# Input.net
KiCad netlist of a schematic drawn in Altium Designer
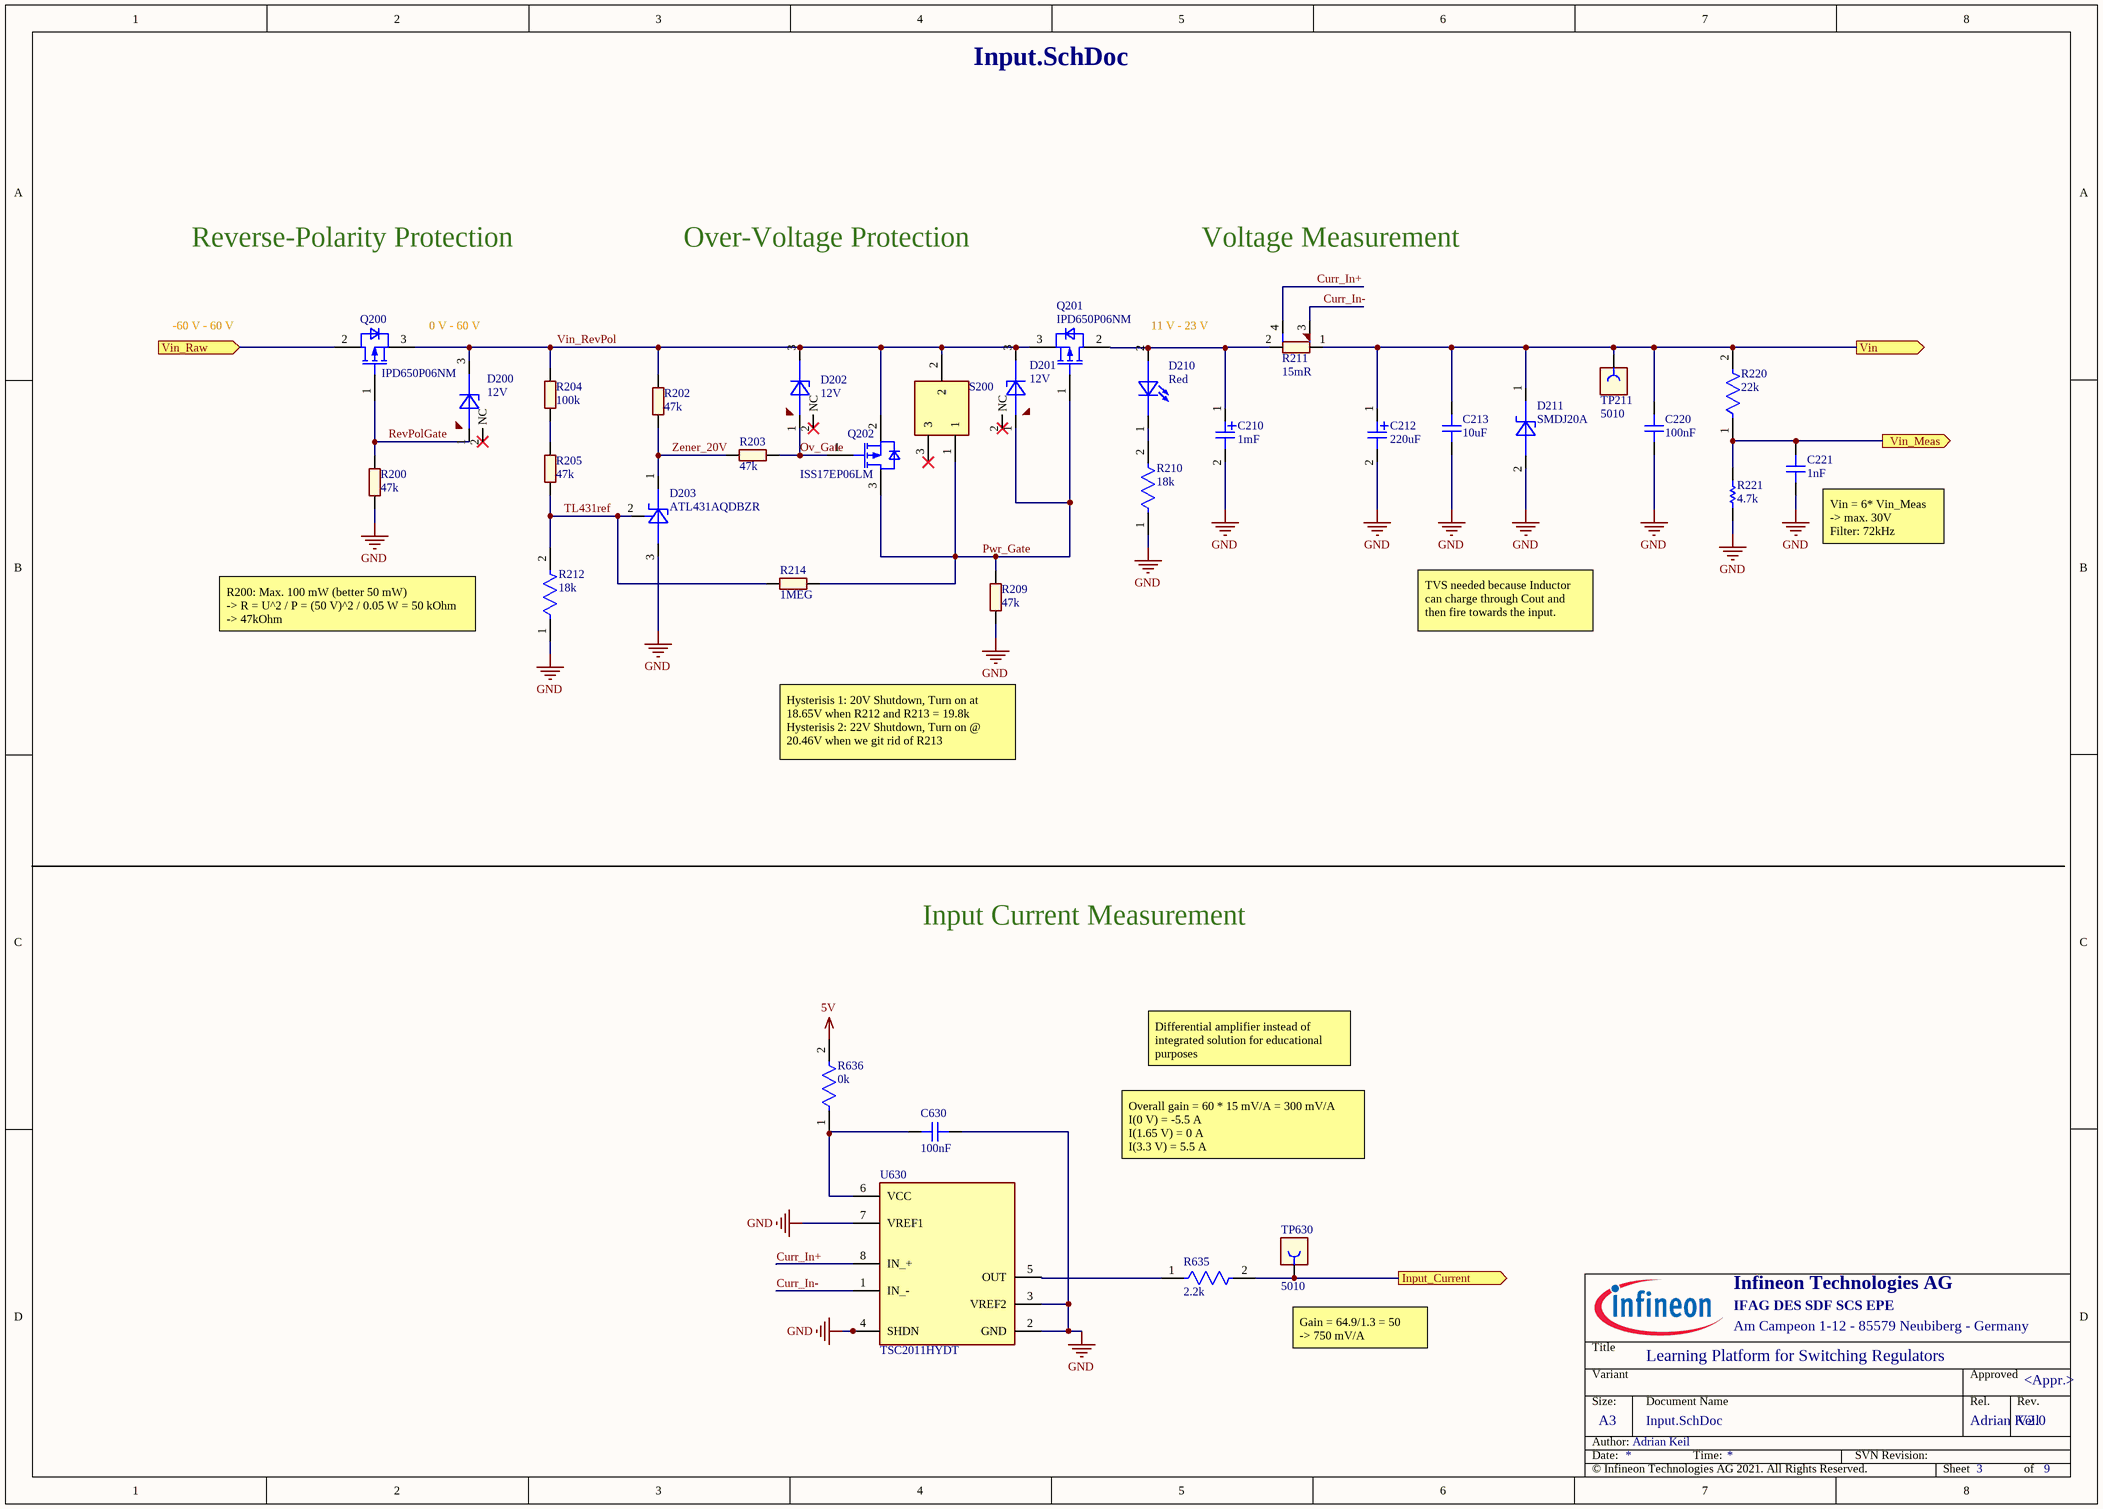
[diagram p0: Input.SchDoc]

(export (version "E")
  (design (tool "Eeschema 10.0.6"))
  (components
    (comp (ref "C210")
      (value "1mF")
      (footprint "CAPPRD500W60D1300H2700B")
      (fields (field (name "MANUFACTURER") "Kemet") (field (name "MPN") "ESY108M035AL4AA"))
      (libsource (lib "PCBLibraryData") (part "CAP-SGL-POL-02P_00000002"))
    )
    (comp (ref "C212")
      (value "220uF")
      (footprint "CAPAE1030X1050N-3")
      (fields
        (field (name "MANUFACTURER") "Nippon Chemi-Con")
        (field (name "LCSC PART #") "C6845235")
        (field (name "MPN") "EMZL500ARA221MJA0G")
      )
      (libsource (lib "PCBLibraryData") (part "CAP-SGL-POL-02P_00000002"))
    )
    (comp (ref "C213")
      (value "10uF")
      (footprint "CAPC3216X190N-1")
      (description "CAP / CERA / 10uF / 50V / 20% / X5R (EIA) / -55°C to 85°C / 1206 (3216) / SMD / -")
      (fields (field (name "MANUFACTURER") "Taiyo Yuden") (field (name "MPN") "UMK316BBJ106ML-T"))
      (libsource (lib "PCBLibraryData") (part "CAP-SGL-STD-02P_00000001"))
    )
    (comp (ref "C220")
      (value "100nF")
      (footprint "CAPC3216X125N-0")
      (description "CAP / CERA / 100nF / 50V / 10% / X7R (EIA) / -55°C to 125°C / 1206(3216) / SMD / -")
      (fields (field (name "LEGACY PARTNUMBER") "CAP01005660") (field (name "MANUFACTURER") "MuRata"))
      (libsource (lib "PCBLibraryData") (part "CAP-SGL-STD-02P_00000001"))
    )
    (comp (ref "C221")
      (value "1nF")
      (footprint "CAPC3216X95N")
      (description "CAP / CERA / 1nF / 50V / 10% / X7R (EIA) / -55°C to 125°C / 1206(3216) / SMD / -")
      (fields (field (name "LEGACY PARTNUMBER") "CAP01005183") (field (name "MANUFACTURER") "MuRata"))
      (libsource (lib "PCBLibraryData") (part "CAP-SGL-STD-02P_00000001"))
    )
    (comp (ref "C630")
      (value "100nF")
      (footprint "CAPC3216X125N-0")
      (description "CAP / CERA / 100nF / 50V / 10% / X7R (EIA) / -55°C to 125°C / 1206(3216) / SMD / -")
      (fields (field (name "LEGACY PARTNUMBER") "CAP01005660") (field (name "MANUFACTURER") "MuRata"))
      (libsource (lib "PCBLibraryData") (part "CAP-SGL-STD-02P_00000001"))
    )
    (comp (ref "D200")
      (value "12V")
      (footprint "SOT95P230X110-3N")
      (description "Voltage regulator diodes")
      (fields (field (name "MANUFACTURER") "Nexperia") (field (name "LCSC PART #") "C12773"))
      (libsource (lib "PCBLibraryData") (part "d_zener_a1c3_3p"))
    )
    (comp (ref "D201")
      (value "12V")
      (footprint "SOT95P230X110-3N")
      (description "Voltage regulator diodes")
      (fields (field (name "MANUFACTURER") "Nexperia"))
      (libsource (lib "PCBLibraryData") (part "d_zener_a1c3_3p"))
    )
    (comp (ref "D202")
      (value "12V")
      (footprint "SOT95P230X110-3N")
      (description "Voltage regulator diodes")
      (fields (field (name "MANUFACTURER") "Nexperia"))
      (libsource (lib "PCBLibraryData") (part "d_zener_a1c3_3p"))
    )
    (comp (ref "D203")
      (value "ATL431AQDBZR")
      (footprint "SOT95P237X112-3N-1")
      (description "ATL431 Adjustable Precision Shunt Regulator")
      (fields (field (name "MANUFACTURER") "Texas Instruments") (field (name "LCSC PART #") "C92572"))
      (libsource (lib "PCBLibraryData") (part "d_tvs_c1a3_3p"))
    )
    (comp (ref "D210")
      (value "Red")
      (footprint "LEDSC160X80X80-2N-1")
      (description "WL-SMCW SMT Mono-color Chip LED Waterclear, Red,630nm")
      (fields (field (name "MANUFACTURER") "Wurth Elektronik") (field (name "LCSC PART #") "C3030991"))
      (libsource (lib "PCBLibraryData") (part "d_led_a"))
    )
    (comp (ref "D211")
      (value "SMDJ20A")
      (footprint "DIOM7959X262N")
      (description "TVS Diode, Low Profile Package, Built in Strain Relief, Glass Passivated Chip Junction")
      (fields (field (name "MANUFACTURER") "Littelfuse") (field (name "LCSC PART #") "C2990194"))
      (libsource (lib "PCBLibraryData") (part "d_tvs_a"))
    )
    (comp (ref "Q200")
      (value "IPD650P06NM")
      (footprint "TO228P998X250-3N-V2")
      (description "OptiMOS Power Transistor, -60 V")
      (fields (field (name "MANUFACTURER") "Infineon Technologies") (field (name "MPN") "IPD650P06NMATMA1"))
      (libsource (lib "PCBLibraryData") (part "igfet_p_ch_enh_dio_1g2d3s_3p"))
    )
    (comp (ref "Q201")
      (value "IPD650P06NM")
      (footprint "TO228P998X250-3N-V2")
      (description "OptiMOS Power Transistor, -60 V")
      (fields (field (name "MANUFACTURER") "Infineon Technologies"))
      (libsource (lib "PCBLibraryData") (part "igfet_p_ch_enh_dio_1g2d3s_3p"))
    )
    (comp (ref "Q202")
      (value "ISS17EP06LM")
      (footprint "SOT95P240X110-3N-1-V")
      (description "OptiMOSTM Small Signal Transistor, -60 V")
      (fields (field (name "MANUFACTURER") "Infineon Technologies") (field (name "MPN") "ISS17EP06LMXTSA1"))
      (libsource (lib "PCBLibraryData") (part "igfet_p_ch_enh_dio_1g2s3d_3p"))
    )
    (comp (ref "R200")
      (value "47k")
      (footprint "RESC3216X60N")
      (description "RES / STD / 47k / 250mW / 1% / 100ppm/K / -55°C to 155°C / 1206(3216) / SMD / -")
      (fields (field (name "LEGACY PARTNUMBER") "RES01802933") (field (name "MANUFACTURER") "Vishay"))
      (libsource (lib "") (part "RES-SGL-STD-02P_00000006_1"))
    )
    (comp (ref "R202")
      (value "47k")
      (footprint "RESC3216X60N")
      (description "RES / STD / 47k / 250mW / 1% / 100ppm/K / -55°C to 155°C / 1206(3216) / SMD / -")
      (fields (field (name "LEGACY PARTNUMBER") "RES01802933") (field (name "MANUFACTURER") "Vishay"))
      (libsource (lib "") (part "RES-SGL-STD-02P_00000006_1"))
    )
    (comp (ref "R203")
      (value "47k")
      (footprint "RESC3216X60N")
      (description "RES / STD / 47k / 250mW / 1% / 100ppm/K / -55°C to 155°C / 1206(3216) / SMD / -")
      (fields (field (name "LEGACY PARTNUMBER") "RES01802933") (field (name "MANUFACTURER") "Vishay"))
      (libsource (lib "") (part "RES-SGL-STD-02P_00000006_2"))
    )
    (comp (ref "R204")
      (value "100k")
      (footprint "RESC3216X60N")
      (description "RES / STD / 100k / 250mW / 1% / 100ppm/K / -55°C to 155°C / 1206(3216) / SMD / -")
      (fields (field (name "LEGACY PARTNUMBER") "RES01802971") (field (name "MANUFACTURER") "Vishay"))
      (libsource (lib "PCBLibraryData") (part "RES-SGL-STD-02P_00000006"))
    )
    (comp (ref "R205")
      (value "47k")
      (footprint "RESC3216X60N")
      (description "RES / STD / 47k / 250mW / 1% / 100ppm/K / -55°C to 155°C / 1206(3216) / SMD / -")
      (fields (field (name "LEGACY PARTNUMBER") "RES01802933") (field (name "MANUFACTURER") "Vishay"))
      (libsource (lib "") (part "RES-SGL-STD-02P_00000006_1"))
    )
    (comp (ref "R209")
      (value "47k")
      (footprint "RESC3216X60N")
      (description "RES / STD / 47k / 250mW / 1% / 100ppm/K / -55°C to 155°C / 1206(3216) / SMD / -")
      (fields (field (name "LEGACY PARTNUMBER") "RES01802933") (field (name "MANUFACTURER") "Vishay"))
      (libsource (lib "") (part "RES-SGL-STD-02P_00000006_1"))
    )
    (comp (ref "R210")
      (value "18k")
      (footprint "FP-CRCW1206-e3-IPC_C")
      (description "RES Thick Film, 18kΩ, 1%, 0.25W, 100ppm/°C, 1206")
      (fields (field (name "TOLERANCE") "1%") (field (name "MPN") "CRCW120618K0FKEA"))
      (libsource (lib "Altium Content Vault") (part "1029c3af85768c4190bb7ad29bc67b5"))
    )
    (comp (ref "R211")
      (value "15mR")
      (footprint "RES-SMD-L4T12")
      (description "RES / STD / 15mR / 500mW / 1% / 75ppm/K / -55°C to 155°C / 1206 (3216) / SMD / -")
      (fields (field (name "MANUFACTURER") "Ohmite") (field (name "MPN") "L4T12FR015FER"))
      (libsource (lib "PCBLibraryData") (part "RES-SHT-STD-04P_00097BE5"))
    )
    (comp (ref "R212")
      (value "18k")
      (footprint "FP-CRCW1206-e3-IPC_C")
      (description "RES Thick Film, 18kΩ, 1%, 0.25W, 100ppm/°C, 1206")
      (fields (field (name "TOLERANCE") "1%"))
      (libsource (lib "Altium Content Vault") (part "1029c3af85768c4190bb7ad29bc67b5"))
    )
    (comp (ref "R214")
      (value "1MEG")
      (footprint "RESC3216X60N")
      (description "RES / STD / 1MEG / 250mW / 1% / 100ppm/K / -55°C to 155°C / 1206(3216) / SMD / -")
      (fields (field (name "LEGACY PARTNUMBER") "RES01803085") (field (name "MANUFACTURER") "Vishay"))
      (libsource (lib "") (part "RES-SGL-STD-02P_00000006_3"))
    )
    (comp (ref "R220")
      (value "22k")
      (footprint "FP-CRCW1206-e3-IPC_A")
      (description "RES Thick Film, 22kΩ, 1%, 0.25W, 100ppm/°C, 1206")
      (fields (field (name "TOLERANCE") "1%") (field (name "LCSC PART #") "C844656"))
      (libsource (lib "Altium Content Vault") (part "1029c3af85768c4190bb7ad29bc67b5"))
    )
    (comp (ref "R221")
      (value "4.7k")
      (footprint "RESC3216X60X45ML15T20")
      (description "Chip Resistor, 4.7 KOhm, +/- 1%, 0.25 W, -55 to 155 degC, 1206 (3216 Metric), RoHS, Tape and Reel")
      (fields (field (name "MANUFACTURER") "Vishay Semiconductor") (field (name "TOLERANCE") "1%"))
      (libsource (lib "Altium Content Vault") (part "RES-2"))
    )
    (comp (ref "R635")
      (value "2.2k")
      (footprint "FP-CRCW1206-e3-IPC_C")
      (description "RES Thick Film, 2.2kΩ, 1%, 0.25W, 100ppm/°C, 1206")
      (fields (field (name "TOLERANCE") "1%"))
      (libsource (lib "Altium Content Vault") (part "1029c3af85768c4190bb7ad29bc67b5"))
    )
    (comp (ref "R636")
      (value "0k")
      (footprint "FP-CRCW1206-e3-IPC_C")
      (description "RES Thick Film, 0Ω, 0.25W, 1206")
      (fields (field (name "TOLERANCE") "1%"))
      (libsource (lib "Altium Content Vault") (part "1029c3af85768c4190bb7ad29bc67b5"))
    )
    (comp (ref "S200")
      (value "500SSP1S2M2QEA")
      (footprint "500SSP1S2M2QEA")
      (description "Connector")
      (fields (field (name "MOUSER PART NUMBER") "612-500SSP1S2M2QEA"))
      (libsource (lib "mySchlib") (part "500SSP1S2M2QEA"))
    )
    (comp (ref "TP211")
      (value "5010")
      (footprint "CON-THT-TP-5010")
      (description "PC Test Point-Multipurpose THT, Red")
      (fields
        (field (name "LEGACY PARTNUMBER") "CON01500529")
        (field (name "MANUFACTURER") "Keystone Electronics Corp.")
      )
      (libsource (lib "") (part "connector_1_f_1"))
    )
    (comp (ref "TP630")
      (value "5010")
      (footprint "CON-THT-TP-5010")
      (description "PC Test Point-Multipurpose THT, Red")
      (fields
        (field (name "LEGACY PARTNUMBER") "CON01500529")
        (field (name "MANUFACTURER") "Keystone Electronics Corp.")
      )
      (libsource (lib "PCBLibraryData") (part "connector_1_f"))
    )
    (comp (ref "U630")
      (value "TSC2011HYDT")
      (footprint "myPcbLib:SOIC127P600X175-8N")
      (description "Integrated Circuit")
      (fields (field (name "MOUSER PART NUMBER") "511-TSC2011HYDT"))
      (libsource (lib "mySchlib") (part "TSC2011HYDT"))
    )
  )
  (nets
    (net (code "1") (name "/Curr_In+") (class "Default")
      (node (ref "R211") (pin "4") (pinfunction "I2_4") (pintype "passive"))
      (node (ref "U630") (pin "8") (pinfunction "IN_+_8") (pintype "passive"))
    )
    (net (code "2") (name "/Curr_In-") (class "Default")
      (node (ref "R211") (pin "3") (pinfunction "I1_3") (pintype "passive"))
      (node (ref "U630") (pin "1") (pinfunction "IN_-_1") (pintype "passive"))
    )
    (net (code "3") (name "/Input_Current") (class "Default")
      (node (ref "R635") (pin "2") (pinfunction "2_2") (pintype "passive"))
      (node (ref "TP630") (pin "1") (pinfunction "1_1") (pintype "passive"))
    )
    (net (code "4") (name "/Ov_Gate") (class "Default")
      (node (ref "D202") (pin "1") (pinfunction "ANODE_1") (pintype "passive"))
      (node (ref "Q202") (pin "1") (pinfunction "GATE_1") (pintype "passive"))
      (node (ref "R203") (pin "1") (pinfunction "1_1") (pintype "passive"))
    )
    (net (code "5") (name "/Pwr_Gate") (class "Default")
      (node (ref "D201") (pin "1") (pinfunction "ANODE_1") (pintype "passive"))
      (node (ref "Q201") (pin "1") (pinfunction "GATE_1") (pintype "passive"))
      (node (ref "Q202") (pin "3") (pinfunction "DRAIN_3") (pintype "passive"))
      (node (ref "R209") (pin "2") (pinfunction "2_2") (pintype "passive"))
      (node (ref "R214") (pin "2") (pinfunction "2_2") (pintype "passive"))
      (node (ref "S200") (pin "1") (pinfunction "1_1") (pintype "passive"))
    )
    (net (code "6") (name "/RevPolGate") (class "Default")
      (node (ref "D200") (pin "1") (pinfunction "ANODE_1") (pintype "passive"))
      (node (ref "Q200") (pin "1") (pinfunction "GATE_1") (pintype "passive"))
      (node (ref "R200") (pin "2") (pinfunction "2_2") (pintype "passive"))
    )
    (net (code "7") (name "/TL431ref") (class "Default")
      (node (ref "D203") (pin "2") (pinfunction "REF_2") (pintype "passive"))
      (node (ref "R205") (pin "1") (pinfunction "1_1") (pintype "passive"))
      (node (ref "R212") (pin "2") (pinfunction "2_2") (pintype "passive"))
      (node (ref "R214") (pin "1") (pinfunction "1_1") (pintype "passive"))
    )
    (net (code "8") (name "/Vin") (class "Default")
      (node (ref "C212") (pin "1") (pinfunction "1_1") (pintype "passive"))
      (node (ref "C213") (pin "2") (pinfunction "2_2") (pintype "passive"))
      (node (ref "C220") (pin "1") (pinfunction "1_1") (pintype "passive"))
      (node (ref "D211") (pin "1") (pinfunction "CATHODE_1") (pintype "passive"))
      (node (ref "R211") (pin "1") (pinfunction "V1_1") (pintype "passive"))
      (node (ref "R220") (pin "2") (pinfunction "2_2") (pintype "passive"))
      (node (ref "TP211") (pin "1") (pinfunction "1_1") (pintype "passive"))
    )
    (net (code "9") (name "/Vin_Meas") (class "Default")
      (node (ref "C221") (pin "2") (pinfunction "2_2") (pintype "passive"))
      (node (ref "R220") (pin "1") (pinfunction "1_1") (pintype "passive"))
      (node (ref "R221") (pin "2") (pinfunction "2_2") (pintype "passive"))
    )
    (net (code "10") (name "/Vin_Raw") (class "Default")
      (node (ref "Q200") (pin "2") (pinfunction "DRAIN_2") (pintype "passive"))
    )
    (net (code "11") (name "/Vin_RevPol") (class "Default")
      (node (ref "D200") (pin "3") (pinfunction "CATHODE_3") (pintype "passive"))
      (node (ref "D201") (pin "3") (pinfunction "CATHODE_3") (pintype "passive"))
      (node (ref "D202") (pin "3") (pinfunction "CATHODE_3") (pintype "passive"))
      (node (ref "Q200") (pin "3") (pinfunction "SOURCE_3") (pintype "passive"))
      (node (ref "Q201") (pin "3") (pinfunction "SOURCE_3") (pintype "passive"))
      (node (ref "Q202") (pin "2") (pinfunction "SOURCE_2") (pintype "passive"))
      (node (ref "R202") (pin "2") (pinfunction "2_2") (pintype "passive"))
      (node (ref "R204") (pin "1") (pinfunction "1_1") (pintype "passive"))
      (node (ref "S200") (pin "2") (pinfunction "2_2") (pintype "passive"))
    )
    (net (code "12") (name "/Zener_20V") (class "Default")
      (node (ref "D203") (pin "1") (pinfunction "CATHODE_1") (pintype "passive"))
      (node (ref "R202") (pin "1") (pinfunction "1_1") (pintype "passive"))
      (node (ref "R203") (pin "2") (pinfunction "2_2") (pintype "passive"))
    )
    (net (code "13") (name "5V") (class "Default")
      (node (ref "R636") (pin "2") (pinfunction "2_2") (pintype "passive"))
    )
    (net (code "14") (name "GND") (class "Default")
      (node (ref "C210") (pin "2") (pinfunction "2_2") (pintype "passive"))
      (node (ref "C212") (pin "2") (pinfunction "2_2") (pintype "passive"))
      (node (ref "C213") (pin "1") (pinfunction "1_1") (pintype "passive"))
      (node (ref "C220") (pin "2") (pinfunction "2_2") (pintype "passive"))
      (node (ref "C221") (pin "1") (pinfunction "1_1") (pintype "passive"))
      (node (ref "C630") (pin "1") (pinfunction "1_1") (pintype "passive"))
      (node (ref "D203") (pin "3") (pinfunction "ANODE_3") (pintype "passive"))
      (node (ref "D211") (pin "2") (pinfunction "ANODE_2") (pintype "passive"))
      (node (ref "R200") (pin "1") (pinfunction "1_1") (pintype "passive"))
      (node (ref "R209") (pin "1") (pinfunction "1_1") (pintype "passive"))
      (node (ref "R210") (pin "1") (pinfunction "1_1") (pintype "passive"))
      (node (ref "R212") (pin "1") (pinfunction "1_1") (pintype "passive"))
      (node (ref "R221") (pin "1") (pinfunction "1_1") (pintype "passive"))
      (node (ref "U630") (pin "2") (pinfunction "GND_2") (pintype "passive"))
      (node (ref "U630") (pin "3") (pinfunction "VREF2_3") (pintype "passive"))
      (node (ref "U630") (pin "4") (pinfunction "SHDN_4") (pintype "passive"))
      (node (ref "U630") (pin "7") (pinfunction "VREF1_7") (pintype "passive"))
    )
    (net (code "15") (name "Net-(D210-Anode)") (class "Default")
      (node (ref "C210") (pin "1") (pinfunction "1_1") (pintype "passive"))
      (node (ref "D210") (pin "2") (pinfunction "Anode_2") (pintype "passive"))
      (node (ref "Q201") (pin "2") (pinfunction "DRAIN_2") (pintype "passive"))
      (node (ref "R211") (pin "2") (pinfunction "V2_2") (pintype "passive"))
    )
    (net (code "16") (name "Net-(D210-Cathode)") (class "Default")
      (node (ref "D210") (pin "1") (pinfunction "Cathode_1") (pintype "passive"))
      (node (ref "R210") (pin "2") (pinfunction "2_2") (pintype "passive"))
    )
    (net (code "17") (name "Net-(R204-Pad2)") (class "Default")
      (node (ref "R204") (pin "2") (pinfunction "2_2") (pintype "passive"))
      (node (ref "R205") (pin "2") (pinfunction "2_2") (pintype "passive"))
    )
    (net (code "18") (name "Net-(U630-OUT)") (class "Default")
      (node (ref "R635") (pin "1") (pinfunction "1_1") (pintype "passive"))
      (node (ref "U630") (pin "5") (pinfunction "OUT_5") (pintype "passive"))
    )
    (net (code "19") (name "Net-(U630-VCC)") (class "Default")
      (node (ref "C630") (pin "2") (pinfunction "2_2") (pintype "passive"))
      (node (ref "R636") (pin "1") (pinfunction "1_1") (pintype "passive"))
      (node (ref "U630") (pin "6") (pinfunction "VCC_6") (pintype "passive"))
    )
    (net (code "20") (name "unconnected-(D200-NC-Pad2)") (class "Default")
      (node (ref "D200") (pin "2") (pinfunction "NC_2") (pintype "passive+no_connect"))
    )
    (net (code "21") (name "unconnected-(D201-NC-Pad2)") (class "Default")
      (node (ref "D201") (pin "2") (pinfunction "NC_2") (pintype "passive+no_connect"))
    )
    (net (code "22") (name "unconnected-(D202-NC-Pad2)") (class "Default")
      (node (ref "D202") (pin "2") (pinfunction "NC_2") (pintype "passive+no_connect"))
    )
    (net (code "23") (name "unconnected-(S200-Pad3)") (class "Default")
      (node (ref "S200") (pin "3") (pinfunction "3_3") (pintype "passive+no_connect"))
    )
  )
)
